# Simple_WiFi_RS232_by_Bruno.net
KiCad netlist of a schematic drawn in EAGLE
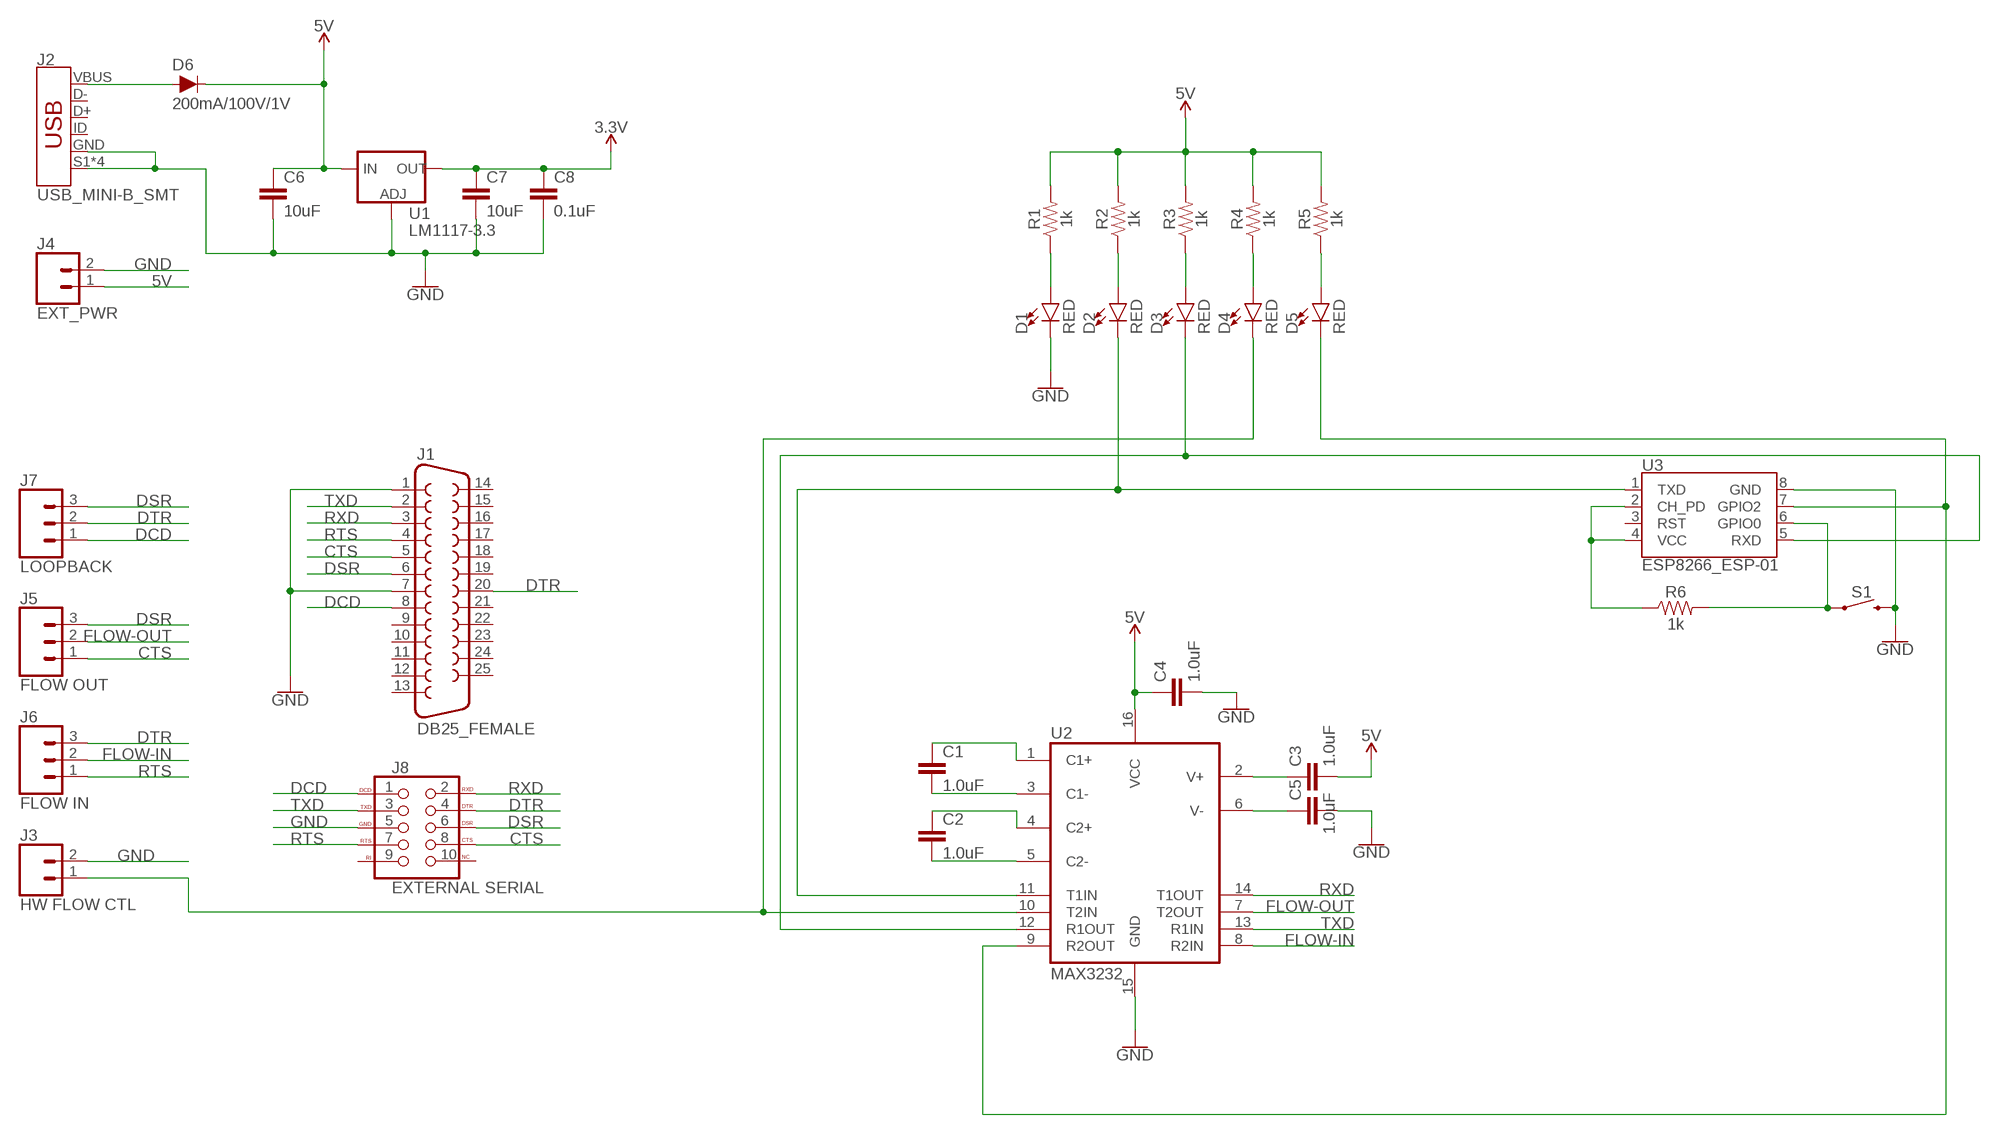
[diagram p0: schematic, sheet 1]

(export (version "E")
  (design (tool "Eeschema 10.0.6"))
  (components
    (comp (ref "C1")
      (value "1.0uF")
      (footprint "eagle-import:0603")
      (libsource (lib "eagle-import") (part "1.0UF-0603-16V-10%"))
    )
    (comp (ref "C2")
      (value "1.0uF")
      (footprint "eagle-import:0603")
      (libsource (lib "eagle-import") (part "1.0UF-0603-16V-10%"))
    )
    (comp (ref "C3")
      (value "1.0uF")
      (footprint "eagle-import:0603")
      (libsource (lib "eagle-import") (part "1.0UF-0603-16V-10%"))
    )
    (comp (ref "C4")
      (value "1.0uF")
      (footprint "eagle-import:0603")
      (libsource (lib "eagle-import") (part "1.0UF-0603-16V-10%"))
    )
    (comp (ref "C5")
      (value "1.0uF")
      (footprint "eagle-import:0603")
      (libsource (lib "eagle-import") (part "1.0UF-0603-16V-10%"))
    )
    (comp (ref "C6")
      (value "10uF")
      (footprint "eagle-import:0603")
      (libsource (lib "eagle-import") (part "10UF-0603-6.3V-20%"))
    )
    (comp (ref "C7")
      (value "10uF")
      (footprint "eagle-import:0603")
      (libsource (lib "eagle-import") (part "10UF-0603-6.3V-20%"))
    )
    (comp (ref "C8")
      (value "0.1uF")
      (footprint "eagle-import:0603")
      (libsource (lib "eagle-import") (part "0.1UF-0603-25V-(+80/-20%)"))
    )
    (comp (ref "D1")
      (value "RED")
      (footprint "eagle-import:LED-0603")
      (libsource (lib "eagle-import") (part "LED-RED0603"))
    )
    (comp (ref "D2")
      (value "RED")
      (footprint "eagle-import:LED-0603")
      (libsource (lib "eagle-import") (part "LED-RED0603"))
    )
    (comp (ref "D3")
      (value "RED")
      (footprint "eagle-import:LED-0603")
      (libsource (lib "eagle-import") (part "LED-RED0603"))
    )
    (comp (ref "D4")
      (value "RED")
      (footprint "eagle-import:LED-0603")
      (libsource (lib "eagle-import") (part "LED-RED0603"))
    )
    (comp (ref "D5")
      (value "RED")
      (footprint "eagle-import:LED-0603")
      (libsource (lib "eagle-import") (part "LED-RED0603"))
    )
    (comp (ref "D6")
      (value "200mA/100V/1V")
      (footprint "eagle-import:DIODE-1N4148")
      (libsource (lib "eagle-import") (part "DIODE-1N4148"))
    )
    (comp (ref "J1")
      (value "DB25_FEMALE")
      (footprint "eagle-import:F25HP")
      (libsource (lib "eagle-import") (part "DB25_FEMALEHP"))
    )
    (comp (ref "J2")
      (value "USB_MINI-B_SMT")
      (footprint "eagle-import:USB-MINIB")
      (libsource (lib "eagle-import") (part "USB_MINI-B_SMT"))
    )
    (comp (ref "J3")
      (value "HW FLOW CTL")
      (footprint "eagle-import:1X02")
      (libsource (lib "eagle-import") (part "CONN_02"))
    )
    (comp (ref "J4")
      (value "EXT_PWR")
      (footprint "eagle-import:1X02")
      (libsource (lib "eagle-import") (part "CONN_02"))
    )
    (comp (ref "J5")
      (value "FLOW OUT")
      (footprint "eagle-import:1X03")
      (libsource (lib "eagle-import") (part "CONN_03"))
    )
    (comp (ref "J6")
      (value "FLOW IN")
      (footprint "eagle-import:1X03")
      (libsource (lib "eagle-import") (part "CONN_03"))
    )
    (comp (ref "J7")
      (value "LOOPBACK")
      (footprint "eagle-import:1X03")
      (libsource (lib "eagle-import") (part "CONN_03"))
    )
    (comp (ref "J8")
      (value "EXTERNAL SERIAL")
      (footprint "eagle-import:2X5-SHROUDED")
      (libsource (lib "eagle-import") (part "10PIN_SERIALPTH2"))
    )
    (comp (ref "R1")
      (value "1k")
      (footprint "eagle-import:0603")
      (libsource (lib "eagle-import") (part "1KOHM-0603-1/10W-1%"))
    )
    (comp (ref "R2")
      (value "1k")
      (footprint "eagle-import:0603")
      (libsource (lib "eagle-import") (part "1KOHM-0603-1/10W-1%"))
    )
    (comp (ref "R3")
      (value "1k")
      (footprint "eagle-import:0603")
      (libsource (lib "eagle-import") (part "1KOHM-0603-1/10W-1%"))
    )
    (comp (ref "R4")
      (value "1k")
      (footprint "eagle-import:0603")
      (libsource (lib "eagle-import") (part "1KOHM-0603-1/10W-1%"))
    )
    (comp (ref "R5")
      (value "1k")
      (footprint "eagle-import:0603")
      (libsource (lib "eagle-import") (part "1KOHM-0603-1/10W-1%"))
    )
    (comp (ref "R6")
      (value "1k")
      (footprint "eagle-import:0603")
      (libsource (lib "eagle-import") (part "1KOHM-0603-1/10W-1%"))
    )
    (comp (ref "S1")
      (value "MOMENTARY-SWITCH-SPST-PTH-6.0MM")
      (footprint "eagle-import:TACTILE_SWITCH_PTH_6.0MM")
      (libsource (lib "eagle-import") (part "MOMENTARY-SWITCH-SPST-PTH-6.0MM"))
    )
    (comp (ref "U1")
      (value "LM1117-3.3")
      (footprint "eagle-import:SOT223")
      (libsource (lib "eagle-import") (part "V_REG_LM1117SOT223"))
    )
    (comp (ref "U2")
      (value "MAX3232")
      (footprint "eagle-import:DIP16")
      (libsource (lib "eagle-import") (part "MAX2323PTH"))
    )
    (comp (ref "U3")
      (value "ESP8266_ESP-01")
      (footprint "eagle-import:ESP8266_ESP-01")
      (libsource (lib "eagle-import") (part "ESP8266_ESP-01"))
    )
  )
  (nets
    (net (code "1") (name "/CTS") (class "Default")
      (node (ref "J1") (pin "5") (pinfunction "5_5") (pintype "passive"))
      (node (ref "J5") (pin "1") (pinfunction "1_1") (pintype "passive"))
      (node (ref "J8") (pin "8") (pinfunction "CTS_8") (pintype "power_in"))
    )
    (net (code "2") (name "/DCD") (class "Default")
      (node (ref "J1") (pin "8") (pinfunction "8_8") (pintype "passive"))
      (node (ref "J7") (pin "1") (pinfunction "1_1") (pintype "passive"))
      (node (ref "J8") (pin "1") (pinfunction "DCD_1") (pintype "power_in"))
    )
    (net (code "3") (name "/DSR") (class "Default")
      (node (ref "J1") (pin "6") (pinfunction "6_6") (pintype "passive"))
      (node (ref "J5") (pin "3") (pinfunction "3_3") (pintype "passive"))
      (node (ref "J7") (pin "3") (pinfunction "3_3") (pintype "passive"))
      (node (ref "J8") (pin "6") (pinfunction "DSR_6") (pintype "power_in"))
    )
    (net (code "4") (name "/DTR") (class "Default")
      (node (ref "J1") (pin "20") (pinfunction "20_20") (pintype "passive"))
      (node (ref "J6") (pin "3") (pinfunction "3_3") (pintype "passive"))
      (node (ref "J7") (pin "2") (pinfunction "2_2") (pintype "passive"))
      (node (ref "J8") (pin "4") (pinfunction "DTR_4") (pintype "output"))
    )
    (net (code "5") (name "/FLOW-IN") (class "Default")
      (node (ref "J6") (pin "2") (pinfunction "2_2") (pintype "passive"))
      (node (ref "U2") (pin "8") (pinfunction "R2IN_8") (pintype "input"))
    )
    (net (code "6") (name "/FLOW-OUT") (class "Default")
      (node (ref "J5") (pin "2") (pinfunction "2_2") (pintype "passive"))
      (node (ref "U2") (pin "7") (pinfunction "T2OUT_7") (pintype "output"))
    )
    (net (code "7") (name "/NC") (class "Default")
      (node (ref "J8") (pin "10") (pinfunction "NC_10") (pintype "power_in"))
    )
    (net (code "8") (name "/RTS") (class "Default")
      (node (ref "J1") (pin "4") (pinfunction "4_4") (pintype "passive"))
      (node (ref "J6") (pin "1") (pinfunction "1_1") (pintype "passive"))
      (node (ref "J8") (pin "7") (pinfunction "RTS_7") (pintype "passive"))
    )
    (net (code "9") (name "/RXD") (class "Default")
      (node (ref "J1") (pin "3") (pinfunction "3_3") (pintype "passive"))
      (node (ref "J8") (pin "2") (pinfunction "RXD_2") (pintype "power_in"))
      (node (ref "U2") (pin "14") (pinfunction "T1OUT_14") (pintype "output"))
    )
    (net (code "10") (name "/TXD") (class "Default")
      (node (ref "J1") (pin "2") (pinfunction "2_2") (pintype "passive"))
      (node (ref "J8") (pin "3") (pinfunction "TXD_3") (pintype "output"))
      (node (ref "U2") (pin "13") (pinfunction "R1IN_13") (pintype "input"))
    )
    (net (code "11") (name "3.3V") (class "Default")
      (node (ref "C7") (pin "1") (pinfunction "1_1") (pintype "passive"))
      (node (ref "C8") (pin "1") (pinfunction "1_1") (pintype "passive"))
      (node (ref "U1") (pin "2") (pinfunction "OUT_2") (pintype "output"))
      (node (ref "U1") (pin "4") (pinfunction "OUT_4") (pintype "output"))
    )
    (net (code "12") (name "5V") (class "Default")
      (node (ref "C3") (pin "2") (pinfunction "2_2") (pintype "passive"))
      (node (ref "C4") (pin "1") (pinfunction "1_1") (pintype "passive"))
      (node (ref "C6") (pin "1") (pinfunction "1_1") (pintype "passive"))
      (node (ref "D6") (pin "C") (pinfunction "C_C") (pintype "passive"))
      (node (ref "J4") (pin "1") (pinfunction "1_1") (pintype "passive"))
      (node (ref "R1") (pin "2") (pinfunction "2_2") (pintype "passive"))
      (node (ref "R2") (pin "2") (pinfunction "2_2") (pintype "passive"))
      (node (ref "R3") (pin "2") (pinfunction "2_2") (pintype "passive"))
      (node (ref "R4") (pin "2") (pinfunction "2_2") (pintype "passive"))
      (node (ref "R5") (pin "2") (pinfunction "2_2") (pintype "passive"))
      (node (ref "U1") (pin "3") (pinfunction "IN_3") (pintype "input"))
      (node (ref "U2") (pin "16") (pinfunction "VCC_16") (pintype "bidirectional"))
    )
    (net (code "13") (name "GND") (class "Default")
      (node (ref "C4") (pin "2") (pinfunction "2_2") (pintype "passive"))
      (node (ref "C5") (pin "2") (pinfunction "2_2") (pintype "passive"))
      (node (ref "C6") (pin "2") (pinfunction "2_2") (pintype "passive"))
      (node (ref "C7") (pin "2") (pinfunction "2_2") (pintype "passive"))
      (node (ref "C8") (pin "2") (pinfunction "2_2") (pintype "passive"))
      (node (ref "D1") (pin "C") (pinfunction "C_C") (pintype "passive"))
      (node (ref "J1") (pin "1") (pinfunction "1_1") (pintype "passive"))
      (node (ref "J1") (pin "7") (pinfunction "7_7") (pintype "passive"))
      (node (ref "J2") (pin "GND") (pinfunction "GND_GND") (pintype "power_in"))
      (node (ref "J2") (pin "S1") (pinfunction "SHIELD_S1") (pintype "bidirectional"))
      (node (ref "J2") (pin "S2") (pinfunction "SHIELD_S2") (pintype "bidirectional"))
      (node (ref "J2") (pin "S3") (pinfunction "SHIELD_S3") (pintype "bidirectional"))
      (node (ref "J2") (pin "S4") (pinfunction "SHIELD_S4") (pintype "bidirectional"))
      (node (ref "J3") (pin "2") (pinfunction "2_2") (pintype "passive"))
      (node (ref "J4") (pin "2") (pinfunction "2_2") (pintype "passive"))
      (node (ref "J8") (pin "5") (pinfunction "GND_5") (pintype "input"))
      (node (ref "S1") (pin "3") (pinfunction "2_3") (pintype "passive"))
      (node (ref "U1") (pin "1") (pinfunction "ADJ_1") (pintype "input"))
      (node (ref "U2") (pin "15") (pinfunction "GND_15") (pintype "bidirectional"))
      (node (ref "U3") (pin "8") (pinfunction "GND_8") (pintype "bidirectional"))
    )
    (net (code "14") (name "Net-(D1-PadA)") (class "Default")
      (node (ref "D1") (pin "A") (pinfunction "A_A") (pintype "passive"))
      (node (ref "R1") (pin "1") (pinfunction "1_1") (pintype "passive"))
    )
    (net (code "15") (name "Net-(D2-PadA)") (class "Default")
      (node (ref "D2") (pin "A") (pinfunction "A_A") (pintype "passive"))
      (node (ref "R2") (pin "1") (pinfunction "1_1") (pintype "passive"))
    )
    (net (code "16") (name "Net-(D3-PadA)") (class "Default")
      (node (ref "D3") (pin "A") (pinfunction "A_A") (pintype "passive"))
      (node (ref "R3") (pin "1") (pinfunction "1_1") (pintype "passive"))
    )
    (net (code "17") (name "Net-(D4-PadA)") (class "Default")
      (node (ref "D4") (pin "A") (pinfunction "A_A") (pintype "passive"))
      (node (ref "R4") (pin "1") (pinfunction "1_1") (pintype "passive"))
    )
    (net (code "18") (name "Net-(D5-PadA)") (class "Default")
      (node (ref "D5") (pin "A") (pinfunction "A_A") (pintype "passive"))
      (node (ref "R5") (pin "1") (pinfunction "1_1") (pintype "passive"))
    )
    (net (code "19") (name "Net-(D6-PadA)") (class "Default")
      (node (ref "D6") (pin "A") (pinfunction "A_A") (pintype "passive"))
      (node (ref "J2") (pin "VBUS") (pinfunction "VBUS_VBUS") (pintype "power_in"))
    )
    (net (code "20") (name "Net-(U2-C1+)") (class "Default")
      (node (ref "C1") (pin "1") (pinfunction "1_1") (pintype "passive"))
      (node (ref "U2") (pin "1") (pinfunction "C1+_1") (pintype "bidirectional"))
    )
    (net (code "21") (name "Net-(U2-C1-)") (class "Default")
      (node (ref "C1") (pin "2") (pinfunction "2_2") (pintype "passive"))
      (node (ref "U2") (pin "3") (pinfunction "C1-_3") (pintype "bidirectional"))
    )
    (net (code "22") (name "Net-(U2-C2+)") (class "Default")
      (node (ref "C2") (pin "1") (pinfunction "1_1") (pintype "passive"))
      (node (ref "U2") (pin "4") (pinfunction "C2+_4") (pintype "bidirectional"))
    )
    (net (code "23") (name "Net-(U2-C2-)") (class "Default")
      (node (ref "C2") (pin "2") (pinfunction "2_2") (pintype "passive"))
      (node (ref "U2") (pin "5") (pinfunction "C2-_5") (pintype "bidirectional"))
    )
    (net (code "24") (name "Net-(U2-R1OUT)") (class "Default")
      (node (ref "D3") (pin "C") (pinfunction "C_C") (pintype "passive"))
      (node (ref "U2") (pin "12") (pinfunction "R1OUT_12") (pintype "output"))
      (node (ref "U3") (pin "5") (pinfunction "RXD_5") (pintype "bidirectional"))
    )
    (net (code "25") (name "Net-(U2-R2OUT)") (class "Default")
      (node (ref "D5") (pin "C") (pinfunction "C_C") (pintype "passive"))
      (node (ref "U2") (pin "9") (pinfunction "R2OUT_9") (pintype "output"))
      (node (ref "U3") (pin "7") (pinfunction "GPIO2_7") (pintype "bidirectional"))
    )
    (net (code "26") (name "Net-(U2-T1IN)") (class "Default")
      (node (ref "D2") (pin "C") (pinfunction "C_C") (pintype "passive"))
      (node (ref "U2") (pin "11") (pinfunction "T1IN_11") (pintype "input"))
      (node (ref "U3") (pin "1") (pinfunction "TXD_1") (pintype "bidirectional"))
    )
    (net (code "27") (name "Net-(U2-T2IN)") (class "Default")
      (node (ref "D4") (pin "C") (pinfunction "C_C") (pintype "passive"))
      (node (ref "J3") (pin "1") (pinfunction "1_1") (pintype "passive"))
      (node (ref "U2") (pin "10") (pinfunction "T2IN_10") (pintype "input"))
    )
    (net (code "28") (name "Net-(U2-V+)") (class "Default")
      (node (ref "C3") (pin "1") (pinfunction "1_1") (pintype "passive"))
      (node (ref "U2") (pin "2") (pinfunction "V+_2") (pintype "bidirectional"))
    )
    (net (code "29") (name "Net-(U2-V-)") (class "Default")
      (node (ref "C5") (pin "1") (pinfunction "1_1") (pintype "passive"))
      (node (ref "U2") (pin "6") (pinfunction "V-_6") (pintype "bidirectional"))
    )
    (net (code "30") (name "Net-(U3-CH_PD)") (class "Default")
      (node (ref "R6") (pin "1") (pinfunction "1_1") (pintype "passive"))
      (node (ref "U3") (pin "2") (pinfunction "CH_PD_2") (pintype "bidirectional"))
      (node (ref "U3") (pin "4") (pinfunction "VCC_4") (pintype "bidirectional"))
    )
    (net (code "31") (name "Net-(U3-GPIO0)") (class "Default")
      (node (ref "R6") (pin "2") (pinfunction "2_2") (pintype "passive"))
      (node (ref "S1") (pin "1") (pinfunction "1_1") (pintype "passive"))
      (node (ref "U3") (pin "6") (pinfunction "GPIO0_6") (pintype "bidirectional"))
    )
    (net (code "32") (name "unconnected-(J1-Pad9)") (class "Default")
      (node (ref "J1") (pin "9") (pinfunction "9_9") (pintype "passive"))
    )
    (net (code "33") (name "unconnected-(J1-Pad10)") (class "Default")
      (node (ref "J1") (pin "10") (pinfunction "10_10") (pintype "passive"))
    )
    (net (code "34") (name "unconnected-(J1-Pad11)") (class "Default")
      (node (ref "J1") (pin "11") (pinfunction "11_11") (pintype "passive"))
    )
    (net (code "35") (name "unconnected-(J1-Pad12)") (class "Default")
      (node (ref "J1") (pin "12") (pinfunction "12_12") (pintype "passive"))
    )
    (net (code "36") (name "unconnected-(J1-Pad13)") (class "Default")
      (node (ref "J1") (pin "13") (pinfunction "13_13") (pintype "passive"))
    )
    (net (code "37") (name "unconnected-(J1-Pad14)") (class "Default")
      (node (ref "J1") (pin "14") (pinfunction "14_14") (pintype "passive"))
    )
    (net (code "38") (name "unconnected-(J1-Pad15)") (class "Default")
      (node (ref "J1") (pin "15") (pinfunction "15_15") (pintype "passive"))
    )
    (net (code "39") (name "unconnected-(J1-Pad16)") (class "Default")
      (node (ref "J1") (pin "16") (pinfunction "16_16") (pintype "passive"))
    )
    (net (code "40") (name "unconnected-(J1-Pad17)") (class "Default")
      (node (ref "J1") (pin "17") (pinfunction "17_17") (pintype "passive"))
    )
    (net (code "41") (name "unconnected-(J1-Pad18)") (class "Default")
      (node (ref "J1") (pin "18") (pinfunction "18_18") (pintype "passive"))
    )
    (net (code "42") (name "unconnected-(J1-Pad19)") (class "Default")
      (node (ref "J1") (pin "19") (pinfunction "19_19") (pintype "passive"))
    )
    (net (code "43") (name "unconnected-(J1-Pad21)") (class "Default")
      (node (ref "J1") (pin "21") (pinfunction "21_21") (pintype "passive"))
    )
    (net (code "44") (name "unconnected-(J1-Pad22)") (class "Default")
      (node (ref "J1") (pin "22") (pinfunction "22_22") (pintype "passive"))
    )
    (net (code "45") (name "unconnected-(J1-Pad23)") (class "Default")
      (node (ref "J1") (pin "23") (pinfunction "23_23") (pintype "passive"))
    )
    (net (code "46") (name "unconnected-(J1-Pad24)") (class "Default")
      (node (ref "J1") (pin "24") (pinfunction "24_24") (pintype "passive"))
    )
    (net (code "47") (name "unconnected-(J1-Pad25)") (class "Default")
      (node (ref "J1") (pin "25") (pinfunction "25_25") (pintype "passive"))
    )
    (net (code "48") (name "unconnected-(J2-PadD+)") (class "Default")
      (node (ref "J2") (pin "D+") (pinfunction "D+_D+") (pintype "bidirectional"))
    )
    (net (code "49") (name "unconnected-(J2-PadD-)") (class "Default")
      (node (ref "J2") (pin "D-") (pinfunction "D-_D-") (pintype "bidirectional"))
    )
    (net (code "50") (name "unconnected-(J2-PadID)") (class "Default")
      (node (ref "J2") (pin "ID") (pinfunction "ID_ID") (pintype "bidirectional"))
    )
    (net (code "51") (name "unconnected-(J8-RI-Pad9)") (class "Default")
      (node (ref "J8") (pin "9") (pinfunction "RI_9") (pintype "passive"))
    )
    (net (code "52") (name "unconnected-(U3-RST-Pad3)") (class "Default")
      (node (ref "U3") (pin "3") (pinfunction "RST_3") (pintype "bidirectional"))
    )
  )
)
